# ESP32CTRL_AD_SCH.net
KiCad netlist of a schematic drawn in Altium Designer
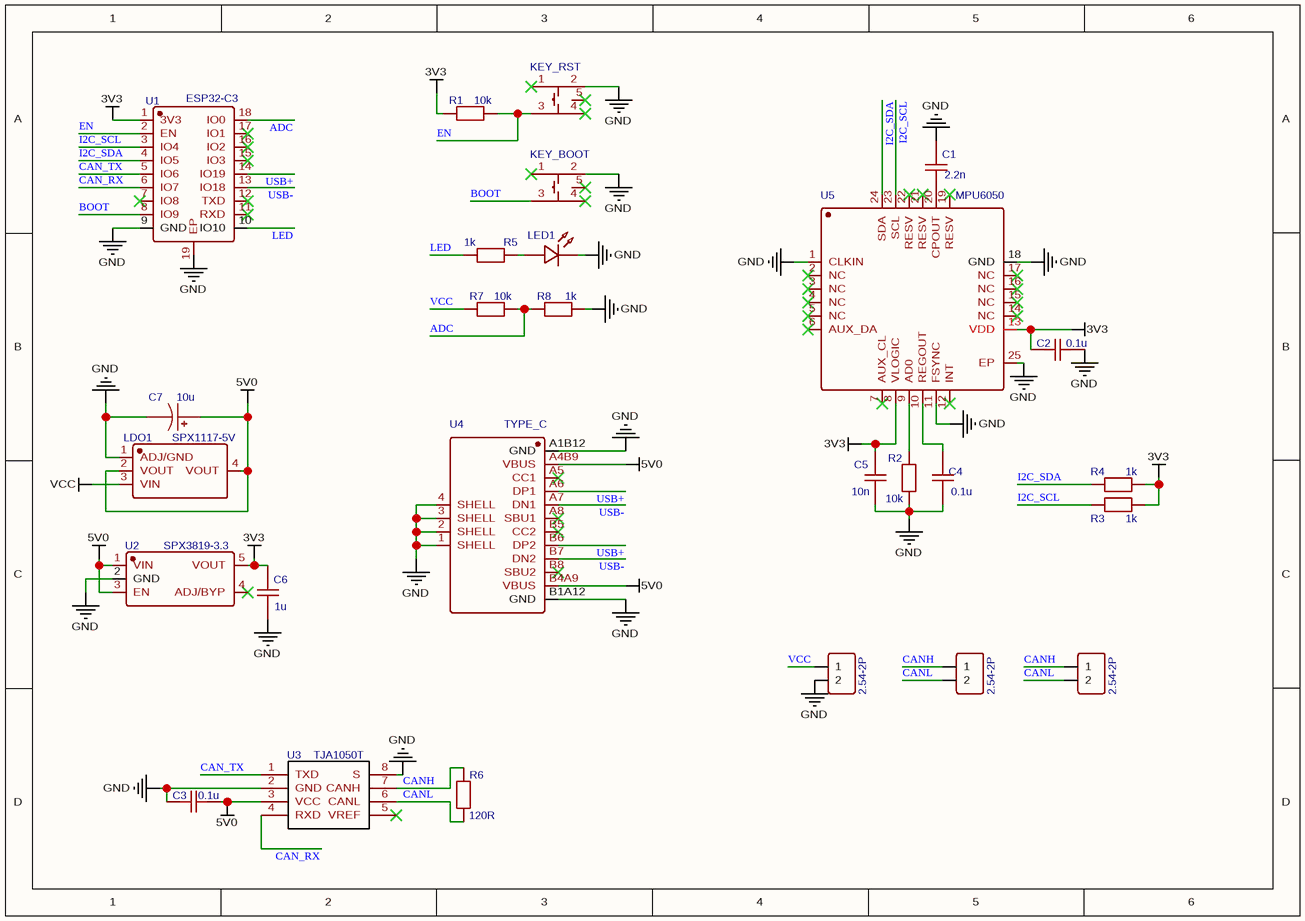
[diagram p0: ESP32CTRL_AD_SCH.schdoc]

(export (version "E")
  (design (tool "Eeschema 10.0.6"))
  (components
    (comp (ref "C1")
      (value "2.2n")
      (fields (field (name "CONTRIBUTOR") "LCEDA_Lib"))
      (libsource (lib "altium-import") (part "root_1_2.2n_"))
    )
    (comp (ref "C2")
      (value "0.1u")
      (fields (field (name "CONTRIBUTOR") "LCEDA_Lib"))
      (libsource (lib "altium-import") (part "root_0_0.1u_"))
    )
    (comp (ref "C3")
      (value "0.1u")
      (fields (field (name "CONTRIBUTOR") "LCEDA_Lib"))
      (libsource (lib "altium-import") (part "root_0_0.1u_"))
    )
    (comp (ref "C4")
      (value "0.1u")
      (fields (field (name "CONTRIBUTOR") "LCEDA_Lib"))
      (libsource (lib "altium-import") (part "root_1_0.1u_"))
    )
    (comp (ref "C5")
      (value "10n")
      (fields (field (name "CONTRIBUTOR") "LCEDA_Lib"))
      (libsource (lib "altium-import") (part "root_1_10n_"))
    )
    (comp (ref "C6")
      (value "1u")
      (fields (field (name "CONTRIBUTOR") "LCEDA_Lib"))
      (libsource (lib "altium-import") (part "root_1_1u_"))
    )
    (comp (ref "C7")
      (value "10u")
      (fields (field (name "CONTRIBUTOR") "LCEDA_Lib"))
      (libsource (lib "altium-import") (part "root_2_10u_"))
    )
    (comp (ref "J1")
      (value "2.54-2P")
      (fields (field (name "BOM_SUPPLIER PART") "C124375") (field (name "CONTRIBUTOR") "LCEDA_Lib"))
      (libsource (lib "altium-import") (part "root_0_2.54-2P_"))
    )
    (comp (ref "J3")
      (value "2.54-2P")
      (fields (field (name "BOM_SUPPLIER PART") "C124375") (field (name "CONTRIBUTOR") "LCEDA_Lib"))
      (libsource (lib "altium-import") (part "root_0_2.54-2P_"))
    )
    (comp (ref "J4")
      (value "2.54-2P")
      (fields (field (name "BOM_SUPPLIER PART") "C124375") (field (name "CONTRIBUTOR") "LCEDA_Lib"))
      (libsource (lib "altium-import") (part "root_0_2.54-2P_"))
    )
    (comp (ref "KEY_BOOT")
      (value "YTSA007A0152501B")
      (fields (field (name "BOM_SUPPLIER PART") "C967768") (field (name "CONTRIBUTOR") "LCSC"))
      (libsource (lib "altium-import") (part "root_0_YTSA007A0152501B_"))
    )
    (comp (ref "KEY_RST")
      (value "YTSA007A0152501B")
      (fields (field (name "BOM_SUPPLIER PART") "C967768") (field (name "CONTRIBUTOR") "LCSC"))
      (libsource (lib "altium-import") (part "root_0_YTSA007A0152501B_"))
    )
    (comp (ref "LDO1")
      (value "SPX1117-5V")
      (fields
        (field (name "BOM_MANUFACTURER PART") "SPX1117M3-L/TR")
        (field (name "BOM_SUPPLIER PART") "C67402")
      )
      (libsource (lib "altium-import") (part "root_0_SPX1117-5V_"))
    )
    (comp (ref "LED1")
      (value "LED-0603_R")
      (fields
        (field (name "BOM_MANUFACTURER PART") "19-217/R6C-AL1M2VY/3T")
        (field (name "BOM_SUPPLIER PART") "C72044")
        (field (name "CONTRIBUTOR") "LCEDA_01")
      )
      (libsource (lib "altium-import") (part "root_2_LED-0603_R_"))
    )
    (comp (ref "R1")
      (value "10k")
      (fields (field (name "CONTRIBUTOR") "LCEDA_Lib"))
      (libsource (lib "altium-import") (part "root_0_10k_"))
    )
    (comp (ref "R2")
      (value "10k")
      (fields (field (name "CONTRIBUTOR") "LCEDA_Lib"))
      (libsource (lib "altium-import") (part "root_1_10k_"))
    )
    (comp (ref "R3")
      (value "1k")
      (fields (field (name "CONTRIBUTOR") "LCEDA_Lib"))
      (libsource (lib "altium-import") (part "root_0_1k_"))
    )
    (comp (ref "R4")
      (value "1k")
      (fields (field (name "CONTRIBUTOR") "LCEDA_Lib"))
      (libsource (lib "altium-import") (part "root_0_1k_"))
    )
    (comp (ref "R5")
      (value "1k")
      (fields (field (name "CONTRIBUTOR") "LCEDA_Lib"))
      (libsource (lib "") (part "root_0_1k__1"))
    )
    (comp (ref "R6")
      (value "120R")
      (fields (field (name "CONTRIBUTOR") "LCEDA_Lib"))
      (libsource (lib "altium-import") (part "root_1_120R_"))
    )
    (comp (ref "R7")
      (value "10k")
      (fields (field (name "CONTRIBUTOR") "LCEDA_Lib"))
      (libsource (lib "altium-import") (part "root_0_10k_"))
    )
    (comp (ref "R8")
      (value "1k")
      (fields (field (name "CONTRIBUTOR") "LCEDA_Lib"))
      (libsource (lib "") (part "root_0_1k__1"))
    )
    (comp (ref "U1")
      (value "ESP32-C3")
      (fields
        (field (name "BOM_SUPPLIER PART") "C9900000362")
        (field (name "BOM_MANUFACTURER PART") "ESP32-C3-WROOM-02-N4")
        (field (name "CONTRIBUTOR") "LCSC")
      )
      (libsource (lib "altium-import") (part "root_0_ESP32-C3_"))
    )
    (comp (ref "U2")
      (value "SPX3819-3.3")
      (fields
        (field (name "BOM_SUPPLIER PART") "C9900018941")
        (field (name "BOM_MANUFACTURER PART") "SPX3819M5-3.3")
        (field (name "CONTRIBUTOR") "lcsc")
      )
      (libsource (lib "altium-import") (part "root_0_SPX3819-3.3_"))
    )
    (comp (ref "U3")
      (value "TJA1050T")
      (fields
        (field (name "BOM_MANUFACTURER PART") "TJA1050T/CM,118")
        (field (name "BOM_SUPPLIER PART") "C6952")
      )
      (libsource (lib "altium-import") (part "root_0_TJA1050T_"))
    )
    (comp (ref "U4")
      (value "TYPE_C")
      (fields
        (field (name "BOM_SUPPLIER PART") "C9900017551")
        (field (name "BOM_MANUFACTURER PART") "TYPE_16/20")
        (field (name "CONTRIBUTOR") "lcsc")
      )
      (libsource (lib "altium-import") (part "root_0_TYPE_C_"))
    )
    (comp (ref "U5")
      (value "MPU6050")
      (fields
        (field (name "BOM_SUPPLIER PART") "C2912107")
        (field (name "BOM_MANUFACTURER PART") "MPU6050-YJLTY")
        (field (name "CONTRIBUTOR") "LCSC")
      )
      (libsource (lib "altium-import") (part "root_0_MPU6050_"))
    )
  )
  (nets
    (net (code "1") (name "/ADC") (class "Default")
      (node (ref "R7") (pin "2") (pinfunction "2_2") (pintype "passive"))
      (node (ref "R8") (pin "2") (pinfunction "2_2") (pintype "passive"))
      (node (ref "U1") (pin "18") (pinfunction "IO0_18") (pintype "passive"))
    )
    (net (code "2") (name "/BOOT") (class "Default")
      (node (ref "KEY_BOOT") (pin "3") (pinfunction "3_3") (pintype "passive"))
      (node (ref "U1") (pin "8") (pinfunction "IO9_8") (pintype "passive"))
    )
    (net (code "3") (name "/CANH") (class "Default")
      (node (ref "J3") (pin "1") (pinfunction "1_1") (pintype "passive"))
      (node (ref "J4") (pin "1") (pinfunction "1_1") (pintype "passive"))
      (node (ref "R6") (pin "2") (pinfunction "2_2") (pintype "passive"))
      (node (ref "U3") (pin "7") (pinfunction "CANH_7") (pintype "passive"))
    )
    (net (code "4") (name "/CANL") (class "Default")
      (node (ref "J3") (pin "2") (pinfunction "2_2") (pintype "passive"))
      (node (ref "J4") (pin "2") (pinfunction "2_2") (pintype "passive"))
      (node (ref "R6") (pin "1") (pinfunction "1_1") (pintype "passive"))
      (node (ref "U3") (pin "6") (pinfunction "CANL_6") (pintype "passive"))
    )
    (net (code "5") (name "/CAN_RX") (class "Default")
      (node (ref "U1") (pin "6") (pinfunction "IO7_6") (pintype "passive"))
      (node (ref "U3") (pin "4") (pinfunction "RXD_4") (pintype "passive"))
    )
    (net (code "6") (name "/CAN_TX") (class "Default")
      (node (ref "U1") (pin "5") (pinfunction "IO6_5") (pintype "passive"))
      (node (ref "U3") (pin "1") (pinfunction "TXD_1") (pintype "passive"))
    )
    (net (code "7") (name "/EN") (class "Default")
      (node (ref "KEY_RST") (pin "3") (pinfunction "3_3") (pintype "passive"))
      (node (ref "R1") (pin "2") (pinfunction "2_2") (pintype "passive"))
      (node (ref "U1") (pin "2") (pinfunction "EN_2") (pintype "passive"))
    )
    (net (code "8") (name "/I2C_SCL") (class "Default")
      (node (ref "R3") (pin "1") (pinfunction "1_1") (pintype "passive"))
      (node (ref "U1") (pin "3") (pinfunction "IO4_3") (pintype "passive"))
      (node (ref "U5") (pin "23") (pinfunction "SCL_23") (pintype "passive"))
    )
    (net (code "9") (name "/I2C_SDA") (class "Default")
      (node (ref "R4") (pin "1") (pinfunction "1_1") (pintype "passive"))
      (node (ref "U1") (pin "4") (pinfunction "IO5_4") (pintype "passive"))
      (node (ref "U5") (pin "24") (pinfunction "SDA_24") (pintype "passive"))
    )
    (net (code "10") (name "/LED") (class "Default")
      (node (ref "R5") (pin "2") (pinfunction "2_2") (pintype "passive"))
      (node (ref "U1") (pin "10") (pinfunction "IO10_10") (pintype "passive"))
    )
    (net (code "11") (name "/USB+") (class "Default")
      (node (ref "U1") (pin "14") (pinfunction "IO19_14") (pintype "passive"))
      (node (ref "U4") (pin "A6") (pinfunction "DP1_A6") (pintype "passive"))
      (node (ref "U4") (pin "B6") (pinfunction "DP2_B6") (pintype "passive"))
    )
    (net (code "12") (name "/USB-") (class "Default")
      (node (ref "U1") (pin "13") (pinfunction "IO18_13") (pintype "passive"))
      (node (ref "U4") (pin "A7") (pinfunction "DN1_A7") (pintype "passive"))
      (node (ref "U4") (pin "B7") (pinfunction "DN2_B7") (pintype "passive"))
    )
    (net (code "13") (name "3V3") (class "Default")
      (node (ref "C2") (pin "1") (pinfunction "1_1") (pintype "passive"))
      (node (ref "C5") (pin "2") (pinfunction "2_2") (pintype "passive"))
      (node (ref "C6") (pin "2") (pinfunction "2_2") (pintype "passive"))
      (node (ref "R1") (pin "1") (pinfunction "1_1") (pintype "passive"))
      (node (ref "R3") (pin "2") (pinfunction "2_2") (pintype "passive"))
      (node (ref "R4") (pin "2") (pinfunction "2_2") (pintype "passive"))
      (node (ref "U1") (pin "1") (pinfunction "3V3_1") (pintype "passive"))
      (node (ref "U2") (pin "5") (pinfunction "VOUT_5") (pintype "passive"))
      (node (ref "U5") (pin "13") (pinfunction "VDD_13") (pintype "passive"))
      (node (ref "U5") (pin "8") (pinfunction "VLOGIC_8") (pintype "passive"))
    )
    (net (code "14") (name "5V0") (class "Default")
      (node (ref "C3") (pin "2") (pinfunction "2_2") (pintype "passive"))
      (node (ref "C7") (pin "1") (pinfunction "1_1") (pintype "passive"))
      (node (ref "LDO1") (pin "2") (pinfunction "VOUT_2") (pintype "passive"))
      (node (ref "LDO1") (pin "4") (pinfunction "VOUT_4") (pintype "passive"))
      (node (ref "U2") (pin "1") (pinfunction "VIN_1") (pintype "passive"))
      (node (ref "U2") (pin "3") (pinfunction "EN_3") (pintype "passive"))
      (node (ref "U3") (pin "3") (pinfunction "VCC_3") (pintype "passive"))
      (node (ref "U4") (pin "A4B9") (pinfunction "VBUS_A4B9") (pintype "passive"))
      (node (ref "U4") (pin "B4A9") (pinfunction "VBUS_B4A9") (pintype "passive"))
    )
    (net (code "15") (name "GND") (class "Default")
      (node (ref "C1") (pin "2") (pinfunction "2_2") (pintype "passive"))
      (node (ref "C2") (pin "2") (pinfunction "2_2") (pintype "passive"))
      (node (ref "C3") (pin "1") (pinfunction "1_1") (pintype "passive"))
      (node (ref "C4") (pin "1") (pinfunction "1_1") (pintype "passive"))
      (node (ref "C5") (pin "1") (pinfunction "1_1") (pintype "passive"))
      (node (ref "C6") (pin "1") (pinfunction "1_1") (pintype "passive"))
      (node (ref "C7") (pin "2") (pinfunction "2_2") (pintype "passive"))
      (node (ref "J1") (pin "2") (pinfunction "2_2") (pintype "passive"))
      (node (ref "KEY_BOOT") (pin "2") (pinfunction "2_2") (pintype "passive"))
      (node (ref "KEY_RST") (pin "2") (pinfunction "2_2") (pintype "passive"))
      (node (ref "LDO1") (pin "1") (pinfunction "ADJ/GND_1") (pintype "passive"))
      (node (ref "LED1") (pin "2") (pinfunction "2_2") (pintype "passive"))
      (node (ref "R2") (pin "1") (pinfunction "1_1") (pintype "passive"))
      (node (ref "R8") (pin "1") (pinfunction "1_1") (pintype "passive"))
      (node (ref "U1") (pin "19") (pinfunction "EP_19") (pintype "passive"))
      (node (ref "U1") (pin "9") (pinfunction "GND_9") (pintype "passive"))
      (node (ref "U2") (pin "2") (pinfunction "GND_2") (pintype "passive"))
      (node (ref "U3") (pin "2") (pinfunction "GND_2") (pintype "passive"))
      (node (ref "U3") (pin "8") (pinfunction "S_8") (pintype "passive"))
      (node (ref "U4") (pin "1") (pinfunction "SHELL_1") (pintype "passive"))
      (node (ref "U4") (pin "2") (pinfunction "SHELL_2") (pintype "passive"))
      (node (ref "U4") (pin "3") (pinfunction "SHELL_3") (pintype "passive"))
      (node (ref "U4") (pin "4") (pinfunction "SHELL_4") (pintype "passive"))
      (node (ref "U4") (pin "A1B12") (pinfunction "GND_A1B12") (pintype "passive"))
      (node (ref "U4") (pin "B1A12") (pinfunction "GND_B1A12") (pintype "passive"))
      (node (ref "U5") (pin "1") (pinfunction "CLKIN_1") (pintype "passive"))
      (node (ref "U5") (pin "11") (pinfunction "FSYNC_11") (pintype "passive"))
      (node (ref "U5") (pin "18") (pinfunction "GND_18") (pintype "passive"))
      (node (ref "U5") (pin "25") (pinfunction "EP_25") (pintype "passive"))
    )
    (net (code "16") (name "Net-(LED1-Pad1)") (class "Default")
      (node (ref "LED1") (pin "1") (pinfunction "1_1") (pintype "passive"))
      (node (ref "R5") (pin "1") (pinfunction "1_1") (pintype "passive"))
    )
    (net (code "17") (name "Net-(U5-AD0)") (class "Default")
      (node (ref "R2") (pin "2") (pinfunction "2_2") (pintype "passive"))
      (node (ref "U5") (pin "9") (pinfunction "AD0_9") (pintype "passive"))
    )
    (net (code "18") (name "Net-(U5-CPOUT)") (class "Default")
      (node (ref "C1") (pin "1") (pinfunction "1_1") (pintype "passive"))
      (node (ref "U5") (pin "20") (pinfunction "CPOUT_20") (pintype "passive"))
    )
    (net (code "19") (name "Net-(U5-REGOUT)") (class "Default")
      (node (ref "C4") (pin "2") (pinfunction "2_2") (pintype "passive"))
      (node (ref "U5") (pin "10") (pinfunction "REGOUT_10") (pintype "passive"))
    )
    (net (code "20") (name "VCC") (class "Default")
      (node (ref "J1") (pin "1") (pinfunction "1_1") (pintype "passive"))
      (node (ref "LDO1") (pin "3") (pinfunction "VIN_3") (pintype "passive"))
      (node (ref "R7") (pin "1") (pinfunction "1_1") (pintype "passive"))
    )
    (net (code "21") (name "unconnected-(KEY_BOOT-Pad1)") (class "Default")
      (node (ref "KEY_BOOT") (pin "1") (pinfunction "1_1") (pintype "passive+no_connect"))
    )
    (net (code "22") (name "unconnected-(KEY_BOOT-Pad4)") (class "Default")
      (node (ref "KEY_BOOT") (pin "4") (pinfunction "4_4") (pintype "passive+no_connect"))
    )
    (net (code "23") (name "unconnected-(KEY_BOOT-Pad5)") (class "Default")
      (node (ref "KEY_BOOT") (pin "5") (pinfunction "5_5") (pintype "passive+no_connect"))
    )
    (net (code "24") (name "unconnected-(KEY_RST-Pad1)") (class "Default")
      (node (ref "KEY_RST") (pin "1") (pinfunction "1_1") (pintype "passive+no_connect"))
    )
    (net (code "25") (name "unconnected-(KEY_RST-Pad4)") (class "Default")
      (node (ref "KEY_RST") (pin "4") (pinfunction "4_4") (pintype "passive+no_connect"))
    )
    (net (code "26") (name "unconnected-(KEY_RST-Pad5)") (class "Default")
      (node (ref "KEY_RST") (pin "5") (pinfunction "5_5") (pintype "passive+no_connect"))
    )
    (net (code "27") (name "unconnected-(U1-IO1-Pad17)") (class "Default")
      (node (ref "U1") (pin "17") (pinfunction "IO1_17") (pintype "passive+no_connect"))
    )
    (net (code "28") (name "unconnected-(U1-IO2-Pad16)") (class "Default")
      (node (ref "U1") (pin "16") (pinfunction "IO2_16") (pintype "passive+no_connect"))
    )
    (net (code "29") (name "unconnected-(U1-IO3-Pad15)") (class "Default")
      (node (ref "U1") (pin "15") (pinfunction "IO3_15") (pintype "passive+no_connect"))
    )
    (net (code "30") (name "unconnected-(U1-IO8-Pad7)") (class "Default")
      (node (ref "U1") (pin "7") (pinfunction "IO8_7") (pintype "passive+no_connect"))
    )
    (net (code "31") (name "unconnected-(U1-RXD-Pad11)") (class "Default")
      (node (ref "U1") (pin "11") (pinfunction "RXD_11") (pintype "passive+no_connect"))
    )
    (net (code "32") (name "unconnected-(U1-TXD-Pad12)") (class "Default")
      (node (ref "U1") (pin "12") (pinfunction "TXD_12") (pintype "passive+no_connect"))
    )
    (net (code "33") (name "unconnected-(U2-ADJ{slash}BYP-Pad4)") (class "Default")
      (node (ref "U2") (pin "4") (pinfunction "ADJ/BYP_4") (pintype "passive+no_connect"))
    )
    (net (code "34") (name "unconnected-(U3-VREF-Pad5)") (class "Default")
      (node (ref "U3") (pin "5") (pinfunction "VREF_5") (pintype "passive+no_connect"))
    )
    (net (code "35") (name "unconnected-(U4-CC1-PadA5)") (class "Default")
      (node (ref "U4") (pin "A5") (pinfunction "CC1_A5") (pintype "passive+no_connect"))
    )
    (net (code "36") (name "unconnected-(U4-CC2-PadB5)") (class "Default")
      (node (ref "U4") (pin "B5") (pinfunction "CC2_B5") (pintype "passive+no_connect"))
    )
    (net (code "37") (name "unconnected-(U4-SBU1-PadA8)") (class "Default")
      (node (ref "U4") (pin "A8") (pinfunction "SBU1_A8") (pintype "passive+no_connect"))
    )
    (net (code "38") (name "unconnected-(U4-SBU2-PadB8)") (class "Default")
      (node (ref "U4") (pin "B8") (pinfunction "SBU2_B8") (pintype "passive+no_connect"))
    )
    (net (code "39") (name "unconnected-(U5-AUX_CL-Pad7)") (class "Default")
      (node (ref "U5") (pin "7") (pinfunction "AUX_CL_7") (pintype "passive+no_connect"))
    )
    (net (code "40") (name "unconnected-(U5-AUX_DA-Pad6)") (class "Default")
      (node (ref "U5") (pin "6") (pinfunction "AUX_DA_6") (pintype "passive+no_connect"))
    )
    (net (code "41") (name "unconnected-(U5-INT-Pad12)") (class "Default")
      (node (ref "U5") (pin "12") (pinfunction "INT_12") (pintype "passive+no_connect"))
    )
    (net (code "42") (name "unconnected-(U5-NC-Pad2)") (class "Default")
      (node (ref "U5") (pin "2") (pinfunction "NC_2") (pintype "passive+no_connect"))
    )
    (net (code "43") (name "unconnected-(U5-NC-Pad3)") (class "Default")
      (node (ref "U5") (pin "3") (pinfunction "NC_3") (pintype "passive+no_connect"))
    )
    (net (code "44") (name "unconnected-(U5-NC-Pad4)") (class "Default")
      (node (ref "U5") (pin "4") (pinfunction "NC_4") (pintype "passive+no_connect"))
    )
    (net (code "45") (name "unconnected-(U5-NC-Pad5)") (class "Default")
      (node (ref "U5") (pin "5") (pinfunction "NC_5") (pintype "passive+no_connect"))
    )
    (net (code "46") (name "unconnected-(U5-NC-Pad14)") (class "Default")
      (node (ref "U5") (pin "14") (pinfunction "NC_14") (pintype "passive+no_connect"))
    )
    (net (code "47") (name "unconnected-(U5-NC-Pad15)") (class "Default")
      (node (ref "U5") (pin "15") (pinfunction "NC_15") (pintype "passive+no_connect"))
    )
    (net (code "48") (name "unconnected-(U5-NC-Pad16)") (class "Default")
      (node (ref "U5") (pin "16") (pinfunction "NC_16") (pintype "passive+no_connect"))
    )
    (net (code "49") (name "unconnected-(U5-NC-Pad17)") (class "Default")
      (node (ref "U5") (pin "17") (pinfunction "NC_17") (pintype "passive+no_connect"))
    )
    (net (code "50") (name "unconnected-(U5-RESV-Pad19)") (class "Default")
      (node (ref "U5") (pin "19") (pinfunction "RESV_19") (pintype "passive+no_connect"))
    )
    (net (code "51") (name "unconnected-(U5-RESV-Pad21)") (class "Default")
      (node (ref "U5") (pin "21") (pinfunction "RESV_21") (pintype "passive+no_connect"))
    )
    (net (code "52") (name "unconnected-(U5-RESV-Pad22)") (class "Default")
      (node (ref "U5") (pin "22") (pinfunction "RESV_22") (pintype "passive+no_connect"))
    )
  )
)
